# Signals.net
KiCad netlist of a schematic drawn in Altium Designer
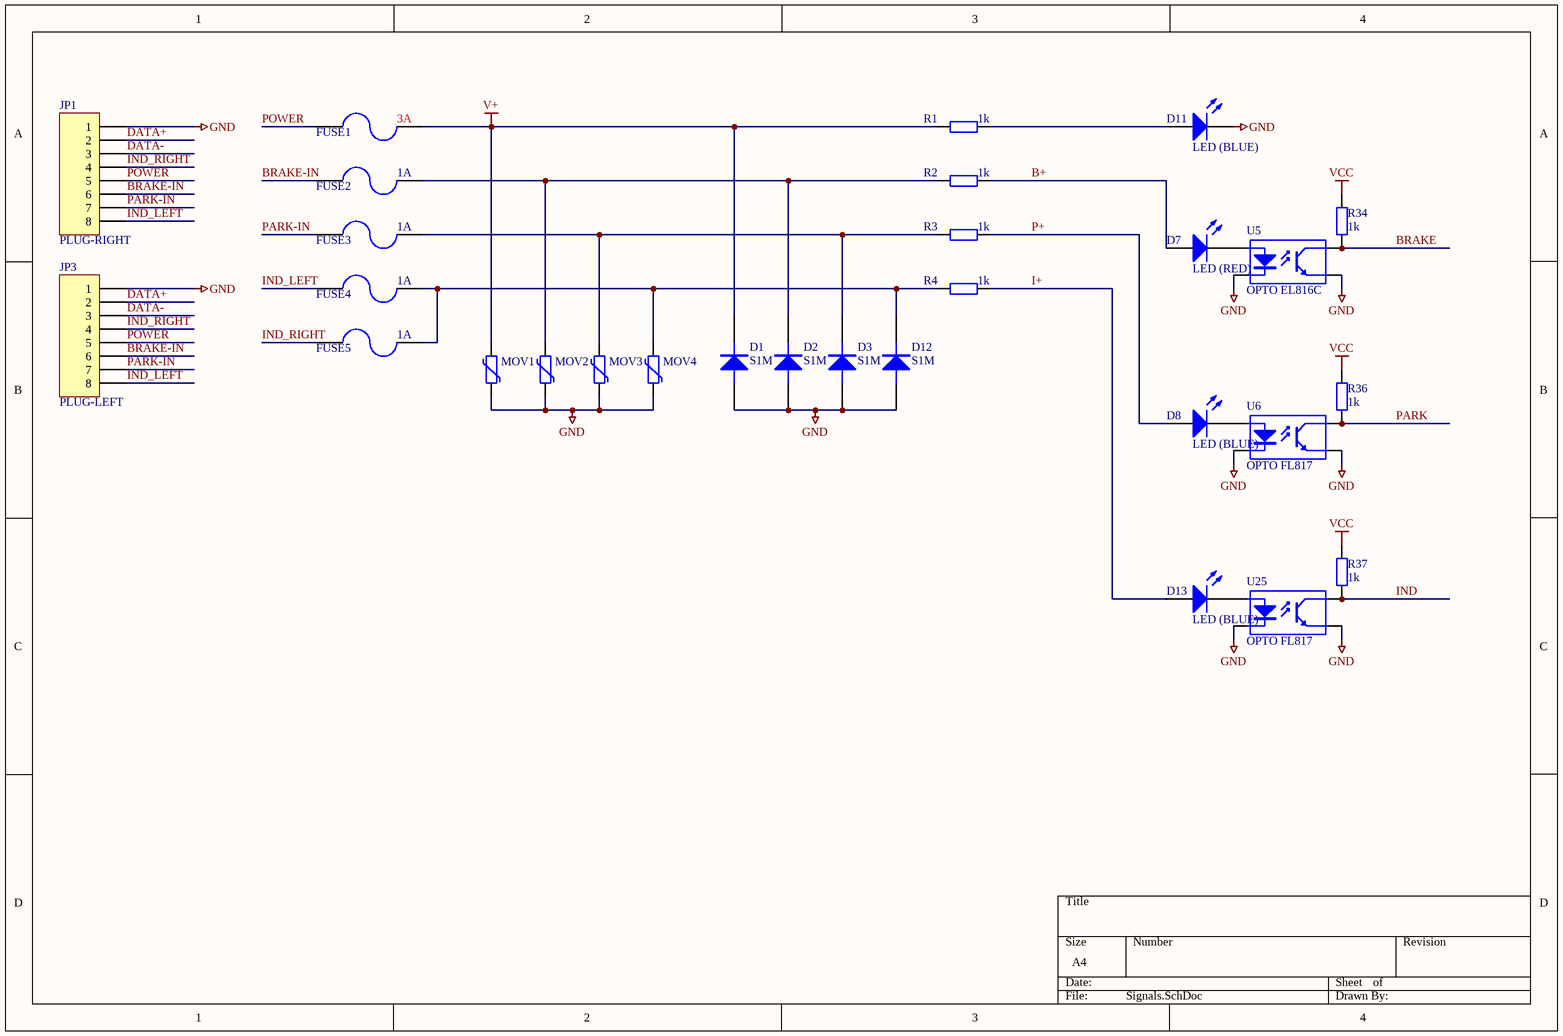
[diagram p0: Signals.SchDoc]

(export (version "E")
  (design (tool "Eeschema 10.0.6"))
  (components
    (comp (ref "D1")
      (value "S1M")
      (footprint "DO-214AC")
      (description "DIODE, POWER")
      (fields (field (name "MOUSER PART NO.") "821-S1M") (field (name "MANUFACTURER") "Taiwan Semiconductor"))
      (libsource (lib "*") (part "DIODE"))
    )
    (comp (ref "D2")
      (value "S1M")
      (footprint "DO-214AC")
      (description "DIODE, POWER")
      (fields (field (name "MOUSER PART NO.") "821-S1M") (field (name "MANUFACTURER") "Taiwan Semiconductor"))
      (libsource (lib "*") (part "DIODE"))
    )
    (comp (ref "D3")
      (value "S1M")
      (footprint "DO-214AC")
      (description "DIODE, POWER")
      (fields (field (name "MOUSER PART NO.") "821-S1M") (field (name "MANUFACTURER") "Taiwan Semiconductor"))
      (libsource (lib "*") (part "DIODE"))
    )
    (comp (ref "D7")
      (value "LED (RED)")
      (footprint "LED(3D) 3MM VERTICAL (GREEN)")
      (description "3mm RED LED")
      (fields (field (name "MOUSER PART NO.") "604-WP132XIT") (field (name "FARNELL PART NO.") "1003393"))
      (libsource (lib "NASCO") (part "LED 3mm RED"))
    )
    (comp (ref "D8")
      (value "LED (BLUE)")
      (footprint "LED(3D) 3MM VERTICAL (GREEN)")
      (description "3mm RED LED")
      (fields (field (name "MOUSER PART NO.") "604-WP132XIT") (field (name "FARNELL PART NO.") "1003393"))
      (libsource (lib "NASCO") (part "LED 3mm RED"))
    )
    (comp (ref "D11")
      (value "LED (BLUE)")
      (footprint "LED(3D) 3MM VERTICAL (GREEN)")
      (description "3mm RED LED")
      (fields (field (name "MOUSER PART NO.") "604-WP132XIT") (field (name "FARNELL PART NO.") "1003393"))
      (libsource (lib "NASCO") (part "LED 3mm RED"))
    )
    (comp (ref "D12")
      (value "S1M")
      (footprint "DO-214AC")
      (description "DIODE, POWER")
      (fields (field (name "MOUSER PART NO.") "821-S1M") (field (name "MANUFACTURER") "Taiwan Semiconductor"))
      (libsource (lib "*") (part "DIODE"))
    )
    (comp (ref "D13")
      (value "LED (BLUE)")
      (footprint "LED(3D) 3MM VERTICAL (GREEN)")
      (description "3mm RED LED")
      (fields (field (name "MOUSER PART NO.") "604-WP132XIT") (field (name "FARNELL PART NO.") "1003393"))
      (libsource (lib "NASCO") (part "LED 3mm RED"))
    )
    (comp (ref "FUSE1")
      (value "3A")
      (footprint "miniSMD Polyswitch")
      (description "POLYSWITCH 1A")
      (fields
        (field (name "MOUSER PART NO.") "650-MINISMDC050F-2")
        (field (name "FARNELL PART NO.") "1175839")
      )
      (libsource (lib "NASCO") (part "POLYSWITCH 500mA"))
    )
    (comp (ref "FUSE2")
      (value "1A")
      (footprint "miniSMD Polyswitch")
      (description "POLYSWITCH 1A")
      (fields
        (field (name "MOUSER PART NO.") "650-MINISMDC050F-2")
        (field (name "FARNELL PART NO.") "1175839")
      )
      (libsource (lib "NASCO") (part "POLYSWITCH 500mA"))
    )
    (comp (ref "FUSE3")
      (value "1A")
      (footprint "miniSMD Polyswitch")
      (description "POLYSWITCH 1A")
      (fields
        (field (name "MOUSER PART NO.") "650-MINISMDC050F-2")
        (field (name "FARNELL PART NO.") "1175839")
      )
      (libsource (lib "NASCO") (part "POLYSWITCH 500mA"))
    )
    (comp (ref "FUSE4")
      (value "1A")
      (footprint "miniSMD Polyswitch")
      (description "POLYSWITCH 1A")
      (fields
        (field (name "MOUSER PART NO.") "650-MINISMDC050F-2")
        (field (name "FARNELL PART NO.") "1175839")
      )
      (libsource (lib "NASCO") (part "POLYSWITCH 500mA"))
    )
    (comp (ref "FUSE5")
      (value "1A")
      (footprint "miniSMD Polyswitch")
      (description "POLYSWITCH 1A")
      (fields
        (field (name "MOUSER PART NO.") "650-MINISMDC050F-2")
        (field (name "FARNELL PART NO.") "1175839")
      )
      (libsource (lib "NASCO") (part "POLYSWITCH 500mA"))
    )
    (comp (ref "JP1")
      (value "PLUG-RIGHT")
      (footprint "Molex 26013144 RA 8P Socket")
      (description "HEADER, 8 WAY")
      (libsource (lib "XC Tail Light Driver") (part "Header 8"))
    )
    (comp (ref "JP3")
      (value "PLUG-LEFT")
      (footprint "Molex 26013144 RA 8P Socket")
      (description "HEADER, 8 WAY")
      (libsource (lib "XC Tail Light Driver") (part "Header 8"))
    )
    (comp (ref "MOV1")
      (value "FTR FTR07D270K 22V")
      (footprint "MOV - 10mm")
      (libsource (lib "LED TAIL LIGHTS") (part "VARISTOR"))
    )
    (comp (ref "MOV2")
      (value "FTR FTR07D270K 22V")
      (footprint "MOV - 10mm")
      (libsource (lib "LED TAIL LIGHTS") (part "VARISTOR"))
    )
    (comp (ref "MOV3")
      (value "FTR FTR07D270K 22V")
      (footprint "MOV - 10mm")
      (libsource (lib "LED TAIL LIGHTS") (part "VARISTOR"))
    )
    (comp (ref "MOV4")
      (value "FTR FTR07D270K 22V")
      (footprint "MOV - 10mm")
      (libsource (lib "LED TAIL LIGHTS") (part "VARISTOR"))
    )
    (comp (ref "R1")
      (value "1k")
      (footprint "RESISTOR 0805")
      (description "Resistor")
      (fields (field (name "PUBLISHER") "Altium Limited"))
      (libsource (lib "Miscellaneous Devices") (part "Res2"))
    )
    (comp (ref "R2")
      (value "1k")
      (footprint "RESISTOR 0805")
      (description "Resistor")
      (fields (field (name "PUBLISHER") "Altium Limited"))
      (libsource (lib "Miscellaneous Devices") (part "Res2"))
    )
    (comp (ref "R3")
      (value "1k")
      (footprint "RESISTOR 0805")
      (description "Resistor")
      (fields (field (name "PUBLISHER") "Altium Limited"))
      (libsource (lib "Miscellaneous Devices") (part "Res2"))
    )
    (comp (ref "R4")
      (value "1k")
      (footprint "RESISTOR 0805")
      (description "Resistor")
      (fields (field (name "PUBLISHER") "Altium Limited"))
      (libsource (lib "Miscellaneous Devices") (part "Res2"))
    )
    (comp (ref "R34")
      (value "1k")
      (footprint "RESISTOR 0805")
      (description "Resistor")
      (fields (field (name "PUBLISHER") "Altium Limited"))
      (libsource (lib "") (part "Res2_1"))
    )
    (comp (ref "R36")
      (value "1k")
      (footprint "RESISTOR 0805")
      (description "Resistor")
      (fields (field (name "PUBLISHER") "Altium Limited"))
      (libsource (lib "") (part "Res2_1"))
    )
    (comp (ref "R37")
      (value "1k")
      (footprint "RESISTOR 0805")
      (description "Resistor")
      (fields (field (name "PUBLISHER") "Altium Limited"))
      (libsource (lib "") (part "Res2_1"))
    )
    (comp (ref "U5")
      (value "OPTO EL816C")
      (footprint "DIP_4")
      (description "4-Pin Phototransistor Optocoupler")
      (fields (field (name "LCSC PART NUMBER") "C181880"))
      (libsource (lib "Schlib1") (part "FL817"))
    )
    (comp (ref "U6")
      (value "OPTO FL817")
      (footprint "DIP_4")
      (description "4-Pin Phototransistor Optocoupler")
      (libsource (lib "Schlib1") (part "FL817"))
    )
    (comp (ref "U25")
      (value "OPTO FL817")
      (footprint "DIP_4")
      (description "4-Pin Phototransistor Optocoupler")
      (libsource (lib "Schlib1") (part "FL817"))
    )
  )
  (nets
    (net (code "1") (name "/B+") (class "Default")
      (node (ref "D7") (pin "1") (pinfunction "A_1") (pintype "passive"))
      (node (ref "R2") (pin "1") (pinfunction "1_1") (pintype "passive"))
    )
    (net (code "2") (name "/BRAKE") (class "Default")
      (node (ref "R34") (pin "2") (pinfunction "2_2") (pintype "passive"))
      (node (ref "U5") (pin "4") (pinfunction "C_4") (pintype "passive"))
    )
    (net (code "3") (name "/BRAKE-IN") (class "Default")
      (node (ref "FUSE2") (pin "1") (pinfunction "1_1") (pintype "passive"))
      (node (ref "JP1") (pin "6") (pinfunction "6_6") (pintype "passive"))
      (node (ref "JP3") (pin "6") (pinfunction "6_6") (pintype "passive"))
    )
    (net (code "4") (name "/DATA+") (class "Default")
      (node (ref "JP1") (pin "2") (pinfunction "2_2") (pintype "passive"))
      (node (ref "JP3") (pin "2") (pinfunction "2_2") (pintype "passive"))
    )
    (net (code "5") (name "/DATA-") (class "Default")
      (node (ref "JP1") (pin "3") (pinfunction "3_3") (pintype "passive"))
      (node (ref "JP3") (pin "3") (pinfunction "3_3") (pintype "passive"))
    )
    (net (code "6") (name "/I+") (class "Default")
      (node (ref "D13") (pin "1") (pinfunction "A_1") (pintype "passive"))
      (node (ref "R4") (pin "1") (pinfunction "1_1") (pintype "passive"))
    )
    (net (code "7") (name "/IND") (class "Default")
      (node (ref "R37") (pin "2") (pinfunction "2_2") (pintype "passive"))
      (node (ref "U25") (pin "4") (pinfunction "C_4") (pintype "passive"))
    )
    (net (code "8") (name "/IND_LEFT") (class "Default")
      (node (ref "FUSE4") (pin "1") (pinfunction "1_1") (pintype "passive"))
      (node (ref "JP1") (pin "8") (pinfunction "8_8") (pintype "passive"))
      (node (ref "JP3") (pin "8") (pinfunction "8_8") (pintype "passive"))
    )
    (net (code "9") (name "/IND_RIGHT") (class "Default")
      (node (ref "FUSE5") (pin "1") (pinfunction "1_1") (pintype "passive"))
      (node (ref "JP1") (pin "4") (pinfunction "4_4") (pintype "passive"))
      (node (ref "JP3") (pin "4") (pinfunction "4_4") (pintype "passive"))
    )
    (net (code "10") (name "/P+") (class "Default")
      (node (ref "D8") (pin "1") (pinfunction "A_1") (pintype "passive"))
      (node (ref "R3") (pin "1") (pinfunction "1_1") (pintype "passive"))
    )
    (net (code "11") (name "/PARK") (class "Default")
      (node (ref "R36") (pin "2") (pinfunction "2_2") (pintype "passive"))
      (node (ref "U6") (pin "4") (pinfunction "C_4") (pintype "passive"))
    )
    (net (code "12") (name "/PARK-IN") (class "Default")
      (node (ref "FUSE3") (pin "1") (pinfunction "1_1") (pintype "passive"))
      (node (ref "JP1") (pin "7") (pinfunction "7_7") (pintype "passive"))
      (node (ref "JP3") (pin "7") (pinfunction "7_7") (pintype "passive"))
    )
    (net (code "13") (name "/POWER") (class "Default")
      (node (ref "FUSE1") (pin "1") (pinfunction "1_1") (pintype "passive"))
      (node (ref "JP1") (pin "5") (pinfunction "5_5") (pintype "passive"))
      (node (ref "JP3") (pin "5") (pinfunction "5_5") (pintype "passive"))
    )
    (net (code "14") (name "GND") (class "Default")
      (node (ref "D1") (pin "1") (pinfunction "A_1") (pintype "passive"))
      (node (ref "D11") (pin "2") (pinfunction "K_2") (pintype "passive"))
      (node (ref "D12") (pin "1") (pinfunction "A_1") (pintype "passive"))
      (node (ref "D2") (pin "1") (pinfunction "A_1") (pintype "passive"))
      (node (ref "D3") (pin "1") (pinfunction "A_1") (pintype "passive"))
      (node (ref "JP1") (pin "1") (pinfunction "1_1") (pintype "passive"))
      (node (ref "JP3") (pin "1") (pinfunction "1_1") (pintype "passive"))
      (node (ref "MOV1") (pin "2") (pinfunction "2_2") (pintype "passive"))
      (node (ref "MOV2") (pin "2") (pinfunction "2_2") (pintype "passive"))
      (node (ref "MOV3") (pin "2") (pinfunction "2_2") (pintype "passive"))
      (node (ref "MOV4") (pin "2") (pinfunction "2_2") (pintype "passive"))
      (node (ref "U25") (pin "2") (pinfunction "K_2") (pintype "passive"))
      (node (ref "U25") (pin "3") (pinfunction "E_3") (pintype "passive"))
      (node (ref "U5") (pin "2") (pinfunction "K_2") (pintype "passive"))
      (node (ref "U5") (pin "3") (pinfunction "E_3") (pintype "passive"))
      (node (ref "U6") (pin "2") (pinfunction "K_2") (pintype "passive"))
      (node (ref "U6") (pin "3") (pinfunction "E_3") (pintype "passive"))
    )
    (net (code "15") (name "Net-(D2-K)") (class "Default")
      (node (ref "D2") (pin "2") (pinfunction "K_2") (pintype "passive"))
      (node (ref "FUSE2") (pin "2") (pinfunction "2_2") (pintype "passive"))
      (node (ref "MOV2") (pin "1") (pinfunction "1_1") (pintype "passive"))
      (node (ref "R2") (pin "2") (pinfunction "2_2") (pintype "passive"))
    )
    (net (code "16") (name "Net-(D3-K)") (class "Default")
      (node (ref "D3") (pin "2") (pinfunction "K_2") (pintype "passive"))
      (node (ref "FUSE3") (pin "2") (pinfunction "2_2") (pintype "passive"))
      (node (ref "MOV3") (pin "1") (pinfunction "1_1") (pintype "passive"))
      (node (ref "R3") (pin "2") (pinfunction "2_2") (pintype "passive"))
    )
    (net (code "17") (name "Net-(D7-K)") (class "Default")
      (node (ref "D7") (pin "2") (pinfunction "K_2") (pintype "passive"))
      (node (ref "U5") (pin "1") (pinfunction "A_1") (pintype "passive"))
    )
    (net (code "18") (name "Net-(D8-K)") (class "Default")
      (node (ref "D8") (pin "2") (pinfunction "K_2") (pintype "passive"))
      (node (ref "U6") (pin "1") (pinfunction "A_1") (pintype "passive"))
    )
    (net (code "19") (name "Net-(D11-A)") (class "Default")
      (node (ref "D11") (pin "1") (pinfunction "A_1") (pintype "passive"))
      (node (ref "R1") (pin "1") (pinfunction "1_1") (pintype "passive"))
    )
    (net (code "20") (name "Net-(D12-K)") (class "Default")
      (node (ref "D12") (pin "2") (pinfunction "K_2") (pintype "passive"))
      (node (ref "FUSE4") (pin "2") (pinfunction "2_2") (pintype "passive"))
      (node (ref "FUSE5") (pin "2") (pinfunction "2_2") (pintype "passive"))
      (node (ref "MOV4") (pin "1") (pinfunction "1_1") (pintype "passive"))
      (node (ref "R4") (pin "2") (pinfunction "2_2") (pintype "passive"))
    )
    (net (code "21") (name "Net-(D13-K)") (class "Default")
      (node (ref "D13") (pin "2") (pinfunction "K_2") (pintype "passive"))
      (node (ref "U25") (pin "1") (pinfunction "A_1") (pintype "passive"))
    )
    (net (code "22") (name "V+") (class "Default")
      (node (ref "D1") (pin "2") (pinfunction "K_2") (pintype "passive"))
      (node (ref "FUSE1") (pin "2") (pinfunction "2_2") (pintype "passive"))
      (node (ref "MOV1") (pin "1") (pinfunction "1_1") (pintype "passive"))
      (node (ref "R1") (pin "2") (pinfunction "2_2") (pintype "passive"))
    )
    (net (code "23") (name "VCC") (class "Default")
      (node (ref "R34") (pin "1") (pinfunction "1_1") (pintype "passive"))
      (node (ref "R36") (pin "1") (pinfunction "1_1") (pintype "passive"))
      (node (ref "R37") (pin "1") (pinfunction "1_1") (pintype "passive"))
    )
  )
)
